# reset.net
KiCad netlist of a schematic drawn in Altium Designer
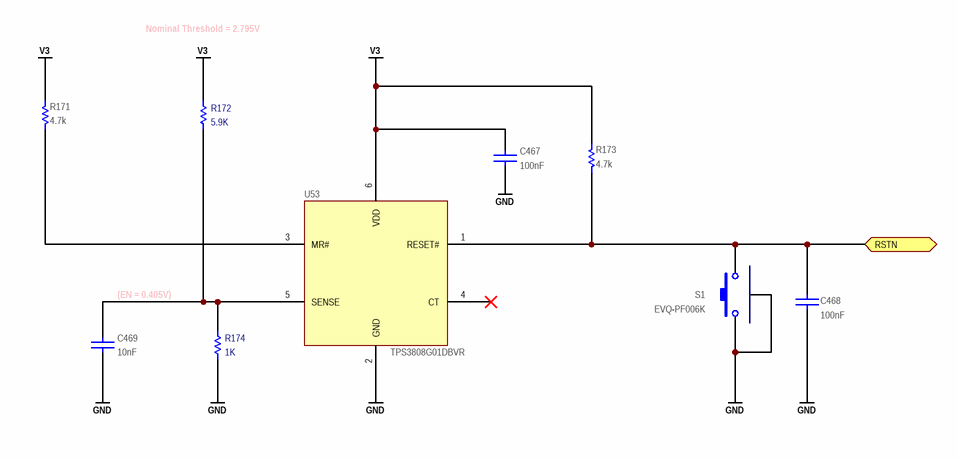
[diagram p0: reset.SchDoc]

(export (version "E")
  (design (tool "Eeschema 10.0.6"))
  (components
    (comp (ref "C467")
      (value "100nF")
      (footprint "CAPC100X50X55L25N")
      (description "Ceramic Capacitor 100nF ±10% 50V X7R 0402")
      (fields (field (name "MANUFACTURER") "Murata") (field (name "TOLERANCE") "±10%"))
      (libsource (lib "") (part "CAP_1"))
    )
    (comp (ref "C468")
      (value "100nF")
      (footprint "CAPC100X50X55L25N")
      (description "Ceramic Capacitor 100nF ±10% 50V X7R 0402")
      (fields (field (name "MANUFACTURER") "Murata") (field (name "TOLERANCE") "±10%"))
      (libsource (lib "generic") (part "CAP"))
    )
    (comp (ref "C469")
      (value "10nF")
      (footprint "CAPC100X50X55L25N")
      (description "Ceramic Capacitor 10nF ±10% 50V X7R 0402")
      (fields (field (name "MANUFACTURER") "Murata") (field (name "TOLERANCE") "±10%"))
      (libsource (lib "") (part "CAP_1"))
    )
    (comp (ref "R171")
      (value "4.7k")
      (footprint "RESC1005X40N")
      (description "Thick Film Resistor 4.7k ±1% 0.1W 75V 0402")
      (fields (field (name "TOLERANCE") "±1%") (field (name "MANUFACTURER") "Panasonic"))
      (libsource (lib "generic") (part "RES"))
    )
    (comp (ref "R172")
      (value "5.9K")
      (footprint "RESC1005X40N")
      (description "Thick Film Resistor 5.9k ±1% 0402")
      (fields (field (name "MANUFACTURER") "Yageo") (field (name "TOLERANCE") "±1%"))
      (libsource (lib "Graviton") (part "RES 0402"))
    )
    (comp (ref "R173")
      (value "4.7k")
      (footprint "RESC1005X40N")
      (description "Thick Film Resistor 4.7k ±1% 0.1W 75V 0402")
      (fields (field (name "TOLERANCE") "±1%") (field (name "MANUFACTURER") "Panasonic"))
      (libsource (lib "generic") (part "RES"))
    )
    (comp (ref "R174")
      (value "1K")
      (footprint "RESC1005X40N")
      (description "Thick Film Resistor 1k ±1% 0402")
      (fields (field (name "MANUFACTURER") "Yageo") (field (name "TOLERANCE") "±1%"))
      (libsource (lib "Graviton") (part "RES 0402"))
    )
    (comp (ref "S1")
      (value "EVQ-PF006K")
      (footprint "EVQ-PF006K")
      (description "Tactile Switch; Normally Open")
      (fields (field (name "MANUFACTURER") "Panasonic"))
      (libsource (lib "panasonic") (part "EVQ-PF006K"))
    )
    (comp (ref "U53")
      (value "TPS3808G01DBVR")
      (footprint "DBV-6")
      (description "Low Quiescent Current, Programmable-Delay  Supervisory Circuit")
      (fields (field (name "MANUFACTURER") "Texas Instruments"))
      (libsource (lib "shit") (part "TPS3808"))
    )
  )
  (nets
    (net (code "1") (name "/RSTN") (class "Default")
      (node (ref "C468") (pin "2") (pinfunction "2_2") (pintype "passive"))
      (node (ref "R173") (pin "1") (pinfunction "1_1") (pintype "passive"))
      (node (ref "S1") (pin "2") (pinfunction "2_2") (pintype "passive"))
      (node (ref "U53") (pin "1") (pinfunction "RESET#_1") (pintype "passive"))
    )
    (net (code "2") (name "GND") (class "Default")
      (node (ref "C467") (pin "2") (pinfunction "2_2") (pintype "passive"))
      (node (ref "C468") (pin "1") (pinfunction "1_1") (pintype "passive"))
      (node (ref "C469") (pin "2") (pinfunction "2_2") (pintype "passive"))
      (node (ref "R174") (pin "1") (pinfunction "1_1") (pintype "passive"))
      (node (ref "S1") (pin "1") (pinfunction "1_1") (pintype "passive"))
      (node (ref "S1") (pin "3") (pinfunction "3_3") (pintype "passive"))
      (node (ref "U53") (pin "2") (pinfunction "GND_2") (pintype "passive"))
    )
    (net (code "3") (name "Net-(U53-MR#)") (class "Default")
      (node (ref "R171") (pin "1") (pinfunction "1_1") (pintype "passive"))
      (node (ref "U53") (pin "3") (pinfunction "MR#_3") (pintype "passive"))
    )
    (net (code "4") (name "Net-(U53-SENSE)") (class "Default")
      (node (ref "C469") (pin "1") (pinfunction "1_1") (pintype "passive"))
      (node (ref "R172") (pin "1") (pinfunction "1_1") (pintype "passive"))
      (node (ref "R174") (pin "2") (pinfunction "2_2") (pintype "passive"))
      (node (ref "U53") (pin "5") (pinfunction "SENSE_5") (pintype "passive"))
    )
    (net (code "5") (name "V3") (class "Default")
      (node (ref "C467") (pin "1") (pinfunction "1_1") (pintype "passive"))
      (node (ref "R171") (pin "2") (pinfunction "2_2") (pintype "passive"))
      (node (ref "R172") (pin "2") (pinfunction "2_2") (pintype "passive"))
      (node (ref "R173") (pin "2") (pinfunction "2_2") (pintype "passive"))
      (node (ref "U53") (pin "6") (pinfunction "VDD_6") (pintype "passive"))
    )
    (net (code "6") (name "unconnected-(U53-CT-Pad4)") (class "Default")
      (node (ref "U53") (pin "4") (pinfunction "CT_4") (pintype "passive+no_connect"))
    )
  )
)
